# motorEncoder.net
KiCad netlist of a schematic drawn in Altium Designer
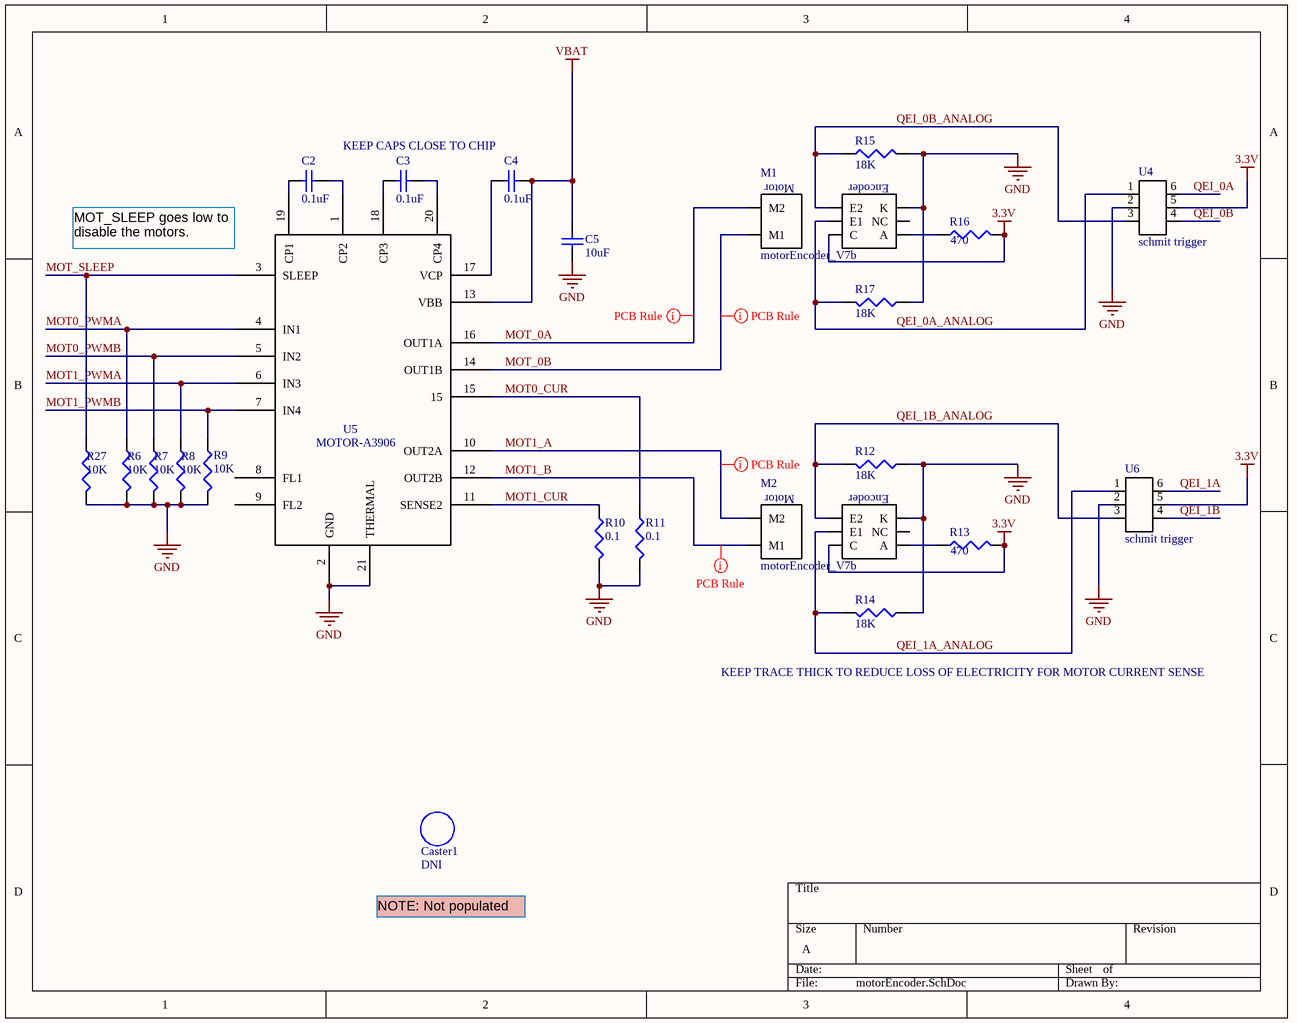
[diagram p0: motorEncoder.SchDoc]

(export (version "E")
  (design (tool "Eeschema 10.0.6"))
  (components
    (comp (ref "C2")
      (value "0.1uF")
      (footprint "CAPC1005L")
      (description "Capacitor (Semiconductor SIM Model)")
      (fields
        (field (name "PART NUMBER") "GRM155R71C104KA88D")
        (field (name "MANUFACTURER") "Murata")
        (field (name "PUBLISHER") "Altium Limited")
      )
      (libsource (lib "Miscellaneous Devices") (part "Cap Semi"))
    )
    (comp (ref "C3")
      (value "0.1uF")
      (footprint "CAPC1005L")
      (description "Capacitor (Semiconductor SIM Model)")
      (fields
        (field (name "PART NUMBER") "GRM155R71C104KA88D")
        (field (name "MANUFACTURER") "Murata")
        (field (name "PUBLISHER") "Altium Limited")
      )
      (libsource (lib "Miscellaneous Devices") (part "Cap Semi"))
    )
    (comp (ref "C4")
      (value "0.1uF")
      (footprint "CAPC1005L")
      (description "Capacitor (Semiconductor SIM Model)")
      (fields
        (field (name "PART NUMBER") "GRM155R71C104KA88D")
        (field (name "MANUFACTURER") "Murata")
        (field (name "PUBLISHER") "Altium Limited")
      )
      (libsource (lib "Miscellaneous Devices") (part "Cap Semi"))
    )
    (comp (ref "C5")
      (value "10uF")
      (footprint "CAPC1608L")
      (description "Capacitor (Semiconductor SIM Model)")
      (fields
        (field (name "PART NUMBER") "GRM188R60J106ME47J")
        (field (name "MANUFACTURER") "Murata")
        (field (name "PUBLISHER") "Altium Limited")
      )
      (libsource (lib "Miscellaneous Devices") (part "Cap Semi"))
    )
    (comp (ref "Caster1")
      (value "non connect")
      (footprint "3/4\"CASTER2")
      (description "This is just a space saver to get the caster onto the pcb")
      (fields
        (field (name "PART NUMBER") "955")
        (field (name "MANUFACTURER") "Pololu")
        (field (name "DNI") "DNI")
      )
      (libsource (lib "mrone") (part "Caster 3/4in"))
    )
    (comp (ref "M1")
      (value "motorEncoder_V7b")
      (footprint "motorEncoder_V7b")
      (fields (field (name "PART NUMBER") "EE-SX1131") (field (name "MANUFACTURER") "Omron"))
      (libsource (lib "mrone") (part "motorEncoder_V7b"))
    )
    (comp (ref "M2")
      (value "motorEncoder_V7b")
      (footprint "motorEncoder_V7b")
      (fields (field (name "PART NUMBER") "EE-SX1131") (field (name "MANUFACTURER") "Omron"))
      (libsource (lib "mrone") (part "motorEncoder_V7b"))
    )
    (comp (ref "R6")
      (value "10K")
      (footprint "RESC1608L")
      (description "Resistor")
      (fields
        (field (name "PART NUMBER") "71-CRCW0603-10K-E3")
        (field (name "MANUFACTURER") "Vishay Dale")
        (field (name "PUBLISHER") "Altium Limited")
      )
      (libsource (lib "Miscellaneous Devices") (part "Res3"))
    )
    (comp (ref "R7")
      (value "10K")
      (footprint "RESC1608L")
      (description "Resistor")
      (fields
        (field (name "PART NUMBER") "71-CRCW0603-10K-E3")
        (field (name "MANUFACTURER") "Vishay Dale")
        (field (name "PUBLISHER") "Altium Limited")
      )
      (libsource (lib "Miscellaneous Devices") (part "Res3"))
    )
    (comp (ref "R8")
      (value "10K")
      (footprint "RESC1608L")
      (description "Resistor")
      (fields
        (field (name "PART NUMBER") "71-CRCW0603-10K-E3")
        (field (name "MANUFACTURER") "Vishay Dale")
        (field (name "PUBLISHER") "Altium Limited")
      )
      (libsource (lib "Miscellaneous Devices") (part "Res3"))
    )
    (comp (ref "R9")
      (value "10K")
      (footprint "RESC1608L")
      (description "Resistor")
      (fields
        (field (name "PART NUMBER") "71-CRCW0603-10K-E3")
        (field (name "MANUFACTURER") "Vishay Dale")
        (field (name "PUBLISHER") "Altium Limited")
      )
      (libsource (lib "Miscellaneous Devices") (part "Res3"))
    )
    (comp (ref "R10")
      (value "0.1")
      (footprint "RESC1608L")
      (description "Resistor")
      (fields
        (field (name "PART NUMBER") "ERJ-3RSJR10V")
        (field (name "MANUFACTURER") "Panasonic")
        (field (name "PUBLISHER") "Altium Limited")
      )
      (libsource (lib "Miscellaneous Devices") (part "Res3"))
    )
    (comp (ref "R11")
      (value "0.1")
      (footprint "RESC1608L")
      (description "Resistor")
      (fields
        (field (name "PART NUMBER") "ERJ-3RSJR10V")
        (field (name "MANUFACTURER") "Panasonic")
        (field (name "PUBLISHER") "Altium Limited")
      )
      (libsource (lib "Miscellaneous Devices") (part "Res3"))
    )
    (comp (ref "R12")
      (value "18K")
      (footprint "RESC1608L")
      (description "Resistor")
      (fields
        (field (name "PART NUMBER") "ERJ-3GEYJ183V")
        (field (name "MANUFACTURER") "Panasonic")
        (field (name "PUBLISHER") "Altium Limited")
      )
      (libsource (lib "Miscellaneous Devices") (part "Res3"))
    )
    (comp (ref "R13")
      (value "470")
      (footprint "RESC1608L")
      (description "Resistor")
      (fields
        (field (name "PART NUMBER") "ERJ-3GEYJ471V")
        (field (name "MANUFACTURER") "Panasonic")
        (field (name "PUBLISHER") "Altium Limited")
      )
      (libsource (lib "Miscellaneous Devices") (part "Res3"))
    )
    (comp (ref "R14")
      (value "18K")
      (footprint "RESC1608L")
      (description "Resistor")
      (fields
        (field (name "PART NUMBER") "ERJ-3GEYJ183V")
        (field (name "MANUFACTURER") "Panasonic")
        (field (name "PUBLISHER") "Altium Limited")
      )
      (libsource (lib "Miscellaneous Devices") (part "Res3"))
    )
    (comp (ref "R15")
      (value "18K")
      (footprint "RESC1608L")
      (description "Resistor")
      (fields
        (field (name "PART NUMBER") "ERJ-3GEYJ183V")
        (field (name "MANUFACTURER") "Panasonic")
        (field (name "PUBLISHER") "Altium Limited")
      )
      (libsource (lib "Miscellaneous Devices") (part "Res3"))
    )
    (comp (ref "R16")
      (value "470")
      (footprint "RESC1608L")
      (description "Resistor")
      (fields
        (field (name "PART NUMBER") "ERJ-3GEYJ471V")
        (field (name "MANUFACTURER") "Panasonic")
        (field (name "PUBLISHER") "Altium Limited")
      )
      (libsource (lib "Miscellaneous Devices") (part "Res3"))
    )
    (comp (ref "R17")
      (value "18K")
      (footprint "RESC1608L")
      (description "Resistor")
      (fields
        (field (name "PART NUMBER") "ERJ-3GEYJ183V")
        (field (name "MANUFACTURER") "Panasonic")
        (field (name "PUBLISHER") "Altium Limited")
      )
      (libsource (lib "Miscellaneous Devices") (part "Res3"))
    )
    (comp (ref "R27")
      (value "10K")
      (footprint "CAPC1608L")
      (description "Resistor")
      (fields
        (field (name "PART NUMBER") "71-CRCW0603-10K-E3")
        (field (name "MANUFACTURER") "Vishay Dale")
        (field (name "PUBLISHER") "Altium Limited")
      )
      (libsource (lib "Miscellaneous Devices") (part "Res3"))
    )
    (comp (ref "U4")
      (value "schmit trigger")
      (footprint "DCK(R-PDSO-C6)")
      (fields (field (name "PART NUMBER") "SN74LVC2G17QDCKRQ1") (field (name "MANUFACTURER") "TI"))
      (libsource (lib "mrone") (part "schmit trigger"))
    )
    (comp (ref "U5")
      (value "MOTOR-A3906")
      (footprint "QFN-20")
      (fields
        (field (name "PART NUMBER") "A3906SESTR-T")
        (field (name "MANUFACTURER") "Allegro Micro Systems")
      )
      (libsource (lib "V2_altium") (part "MOTOR-A3906"))
    )
    (comp (ref "U6")
      (value "schmit trigger")
      (footprint "DCK(R-PDSO-C6)")
      (fields (field (name "PART NUMBER") "SN74LVC2G17QDCKRQ1") (field (name "MANUFACTURER") "TI"))
      (libsource (lib "mrone") (part "schmit trigger"))
    )
  )
  (nets
    (net (code "2") (name "/MOT0_CUR") (class "Default")
      (node (ref "R11") (pin "1") (pinfunction "1_1") (pintype "passive"))
      (node (ref "U5") (pin "15") (pinfunction "15_15") (pintype "passive"))
    )
    (net (code "3") (name "/MOT0_PWMA") (class "Default")
      (node (ref "R6") (pin "1") (pinfunction "1_1") (pintype "passive"))
      (node (ref "U5") (pin "4") (pinfunction "IN1_4") (pintype "passive"))
    )
    (net (code "4") (name "/MOT0_PWMB") (class "Default")
      (node (ref "R7") (pin "1") (pinfunction "1_1") (pintype "passive"))
      (node (ref "U5") (pin "5") (pinfunction "IN2_5") (pintype "passive"))
    )
    (net (code "5") (name "/MOT1_A") (class "Default")
      (node (ref "M2") (pin "M2") (pinfunction "M2_M2") (pintype "passive"))
      (node (ref "U5") (pin "10") (pinfunction "OUT2A_10") (pintype "passive"))
    )
    (net (code "6") (name "/MOT1_B") (class "Default")
      (node (ref "M2") (pin "M1") (pinfunction "M1_M1") (pintype "passive"))
      (node (ref "U5") (pin "12") (pinfunction "OUT2B_12") (pintype "passive"))
    )
    (net (code "7") (name "/MOT1_CUR") (class "Default")
      (node (ref "R10") (pin "1") (pinfunction "1_1") (pintype "passive"))
      (node (ref "U5") (pin "11") (pinfunction "SENSE2_11") (pintype "passive"))
    )
    (net (code "8") (name "/MOT1_PWMA") (class "Default")
      (node (ref "R8") (pin "1") (pinfunction "1_1") (pintype "passive"))
      (node (ref "U5") (pin "6") (pinfunction "IN3_6") (pintype "passive"))
    )
    (net (code "9") (name "/MOT1_PWMB") (class "Default")
      (node (ref "R9") (pin "1") (pinfunction "1_1") (pintype "passive"))
      (node (ref "U5") (pin "7") (pinfunction "IN4_7") (pintype "passive"))
    )
    (net (code "10") (name "/MOT_0A") (class "Default")
      (node (ref "M1") (pin "M2") (pinfunction "M2_M2") (pintype "passive"))
      (node (ref "U5") (pin "16") (pinfunction "OUT1A_16") (pintype "passive"))
    )
    (net (code "11") (name "/MOT_0B") (class "Default")
      (node (ref "M1") (pin "M1") (pinfunction "M1_M1") (pintype "passive"))
      (node (ref "U5") (pin "14") (pinfunction "OUT1B_14") (pintype "passive"))
    )
    (net (code "12") (name "/MOT_SLEEP") (class "Default")
      (node (ref "R27") (pin "1") (pinfunction "1_1") (pintype "passive"))
      (node (ref "U5") (pin "3") (pinfunction "SLEEP_3") (pintype "passive"))
    )
    (net (code "13") (name "/QEI_0A") (class "Default")
      (node (ref "U4") (pin "6") (pinfunction "4_6") (pintype "passive"))
    )
    (net (code "14") (name "/QEI_0A_ANALOG") (class "Default")
      (node (ref "M1") (pin "E1") (pinfunction "E1_E1") (pintype "passive"))
      (node (ref "R17") (pin "2") (pinfunction "2_2") (pintype "passive"))
      (node (ref "U4") (pin "1") (pinfunction "1_1") (pintype "passive"))
    )
    (net (code "15") (name "/QEI_0B") (class "Default")
      (node (ref "U4") (pin "4") (pinfunction "4_4") (pintype "passive"))
    )
    (net (code "16") (name "/QEI_0B_ANALOG") (class "Default")
      (node (ref "M1") (pin "E2") (pinfunction "E2_E2") (pintype "passive"))
      (node (ref "R15") (pin "1") (pinfunction "1_1") (pintype "passive"))
      (node (ref "U4") (pin "3") (pinfunction "3_3") (pintype "passive"))
    )
    (net (code "17") (name "/QEI_1A") (class "Default")
      (node (ref "U6") (pin "6") (pinfunction "4_6") (pintype "passive"))
    )
    (net (code "18") (name "/QEI_1A_ANALOG") (class "Default")
      (node (ref "M2") (pin "E1") (pinfunction "E1_E1") (pintype "passive"))
      (node (ref "R14") (pin "2") (pinfunction "2_2") (pintype "passive"))
      (node (ref "U6") (pin "1") (pinfunction "1_1") (pintype "passive"))
    )
    (net (code "19") (name "/QEI_1B") (class "Default")
      (node (ref "U6") (pin "4") (pinfunction "4_4") (pintype "passive"))
    )
    (net (code "20") (name "/QEI_1B_ANALOG") (class "Default")
      (node (ref "M2") (pin "E2") (pinfunction "E2_E2") (pintype "passive"))
      (node (ref "R12") (pin "2") (pinfunction "2_2") (pintype "passive"))
      (node (ref "U6") (pin "3") (pinfunction "3_3") (pintype "passive"))
    )
    (net (code "21") (name "3.3V") (class "Default")
      (node (ref "M1") (pin "C") (pinfunction "C_C") (pintype "passive"))
      (node (ref "M2") (pin "C") (pinfunction "C_C") (pintype "passive"))
      (node (ref "R13") (pin "2") (pinfunction "2_2") (pintype "passive"))
      (node (ref "R16") (pin "2") (pinfunction "2_2") (pintype "passive"))
      (node (ref "U4") (pin "5") (pinfunction "5_5") (pintype "passive"))
      (node (ref "U6") (pin "5") (pinfunction "5_5") (pintype "passive"))
    )
    (net (code "22") (name "GND") (class "Default")
      (node (ref "C5") (pin "1") (pinfunction "1_1") (pintype "passive"))
      (node (ref "M1") (pin "K") (pinfunction "K_K") (pintype "passive"))
      (node (ref "M2") (pin "K") (pinfunction "K_K") (pintype "passive"))
      (node (ref "R10") (pin "2") (pinfunction "2_2") (pintype "passive"))
      (node (ref "R11") (pin "2") (pinfunction "2_2") (pintype "passive"))
      (node (ref "R12") (pin "1") (pinfunction "1_1") (pintype "passive"))
      (node (ref "R14") (pin "1") (pinfunction "1_1") (pintype "passive"))
      (node (ref "R15") (pin "2") (pinfunction "2_2") (pintype "passive"))
      (node (ref "R17") (pin "1") (pinfunction "1_1") (pintype "passive"))
      (node (ref "R27") (pin "2") (pinfunction "2_2") (pintype "passive"))
      (node (ref "R6") (pin "2") (pinfunction "2_2") (pintype "passive"))
      (node (ref "R7") (pin "2") (pinfunction "2_2") (pintype "passive"))
      (node (ref "R8") (pin "2") (pinfunction "2_2") (pintype "passive"))
      (node (ref "R9") (pin "2") (pinfunction "2_2") (pintype "passive"))
      (node (ref "U4") (pin "2") (pinfunction "2_2") (pintype "passive"))
      (node (ref "U5") (pin "2") (pinfunction "GND_2") (pintype "passive"))
      (node (ref "U5") (pin "21") (pinfunction "THERMAL_21") (pintype "passive"))
      (node (ref "U6") (pin "2") (pinfunction "2_2") (pintype "passive"))
    )
    (net (code "23") (name "Net-(M1-PadA)") (class "Default")
      (node (ref "M1") (pin "A") (pinfunction "A_A") (pintype "passive"))
      (node (ref "R16") (pin "1") (pinfunction "1_1") (pintype "passive"))
    )
    (net (code "24") (name "Net-(M2-PadA)") (class "Default")
      (node (ref "M2") (pin "A") (pinfunction "A_A") (pintype "passive"))
      (node (ref "R13") (pin "1") (pinfunction "1_1") (pintype "passive"))
    )
    (net (code "25") (name "Net-(U5-CP1)") (class "Default")
      (node (ref "C2") (pin "1") (pinfunction "1_1") (pintype "passive"))
      (node (ref "U5") (pin "19") (pinfunction "CP1_19") (pintype "passive"))
    )
    (net (code "26") (name "Net-(U5-CP2)") (class "Default")
      (node (ref "C2") (pin "2") (pinfunction "2_2") (pintype "passive"))
      (node (ref "U5") (pin "1") (pinfunction "CP2_1") (pintype "passive"))
    )
    (net (code "27") (name "Net-(U5-CP3)") (class "Default")
      (node (ref "C3") (pin "1") (pinfunction "1_1") (pintype "passive"))
      (node (ref "U5") (pin "18") (pinfunction "CP3_18") (pintype "passive"))
    )
    (net (code "28") (name "Net-(U5-CP4)") (class "Default")
      (node (ref "C3") (pin "2") (pinfunction "2_2") (pintype "passive"))
      (node (ref "U5") (pin "20") (pinfunction "CP4_20") (pintype "passive"))
    )
    (net (code "29") (name "Net-(U5-VCP)") (class "Default")
      (node (ref "C4") (pin "2") (pinfunction "2_2") (pintype "passive"))
      (node (ref "U5") (pin "17") (pinfunction "VCP_17") (pintype "passive"))
    )
    (net (code "30") (name "VBAT") (class "Default")
      (node (ref "C4") (pin "1") (pinfunction "1_1") (pintype "passive"))
      (node (ref "C5") (pin "2") (pinfunction "2_2") (pintype "passive"))
      (node (ref "U5") (pin "13") (pinfunction "VBB_13") (pintype "passive"))
    )
    (net (code "31") (name "unconnected-(M1-PadNC)") (class "Default")
      (node (ref "M1") (pin "NC") (pinfunction "NC_NC") (pintype "passive"))
    )
    (net (code "32") (name "unconnected-(M2-PadNC)") (class "Default")
      (node (ref "M2") (pin "NC") (pinfunction "NC_NC") (pintype "passive"))
    )
    (net (code "33") (name "unconnected-(U5-FL1-Pad8)") (class "Default")
      (node (ref "U5") (pin "8") (pinfunction "FL1_8") (pintype "passive"))
    )
    (net (code "34") (name "unconnected-(U5-FL2-Pad9)") (class "Default")
      (node (ref "U5") (pin "9") (pinfunction "FL2_9") (pintype "passive"))
    )
  )
)
